# linesensor2b.net
KiCad netlist of a schematic drawn in EAGLE
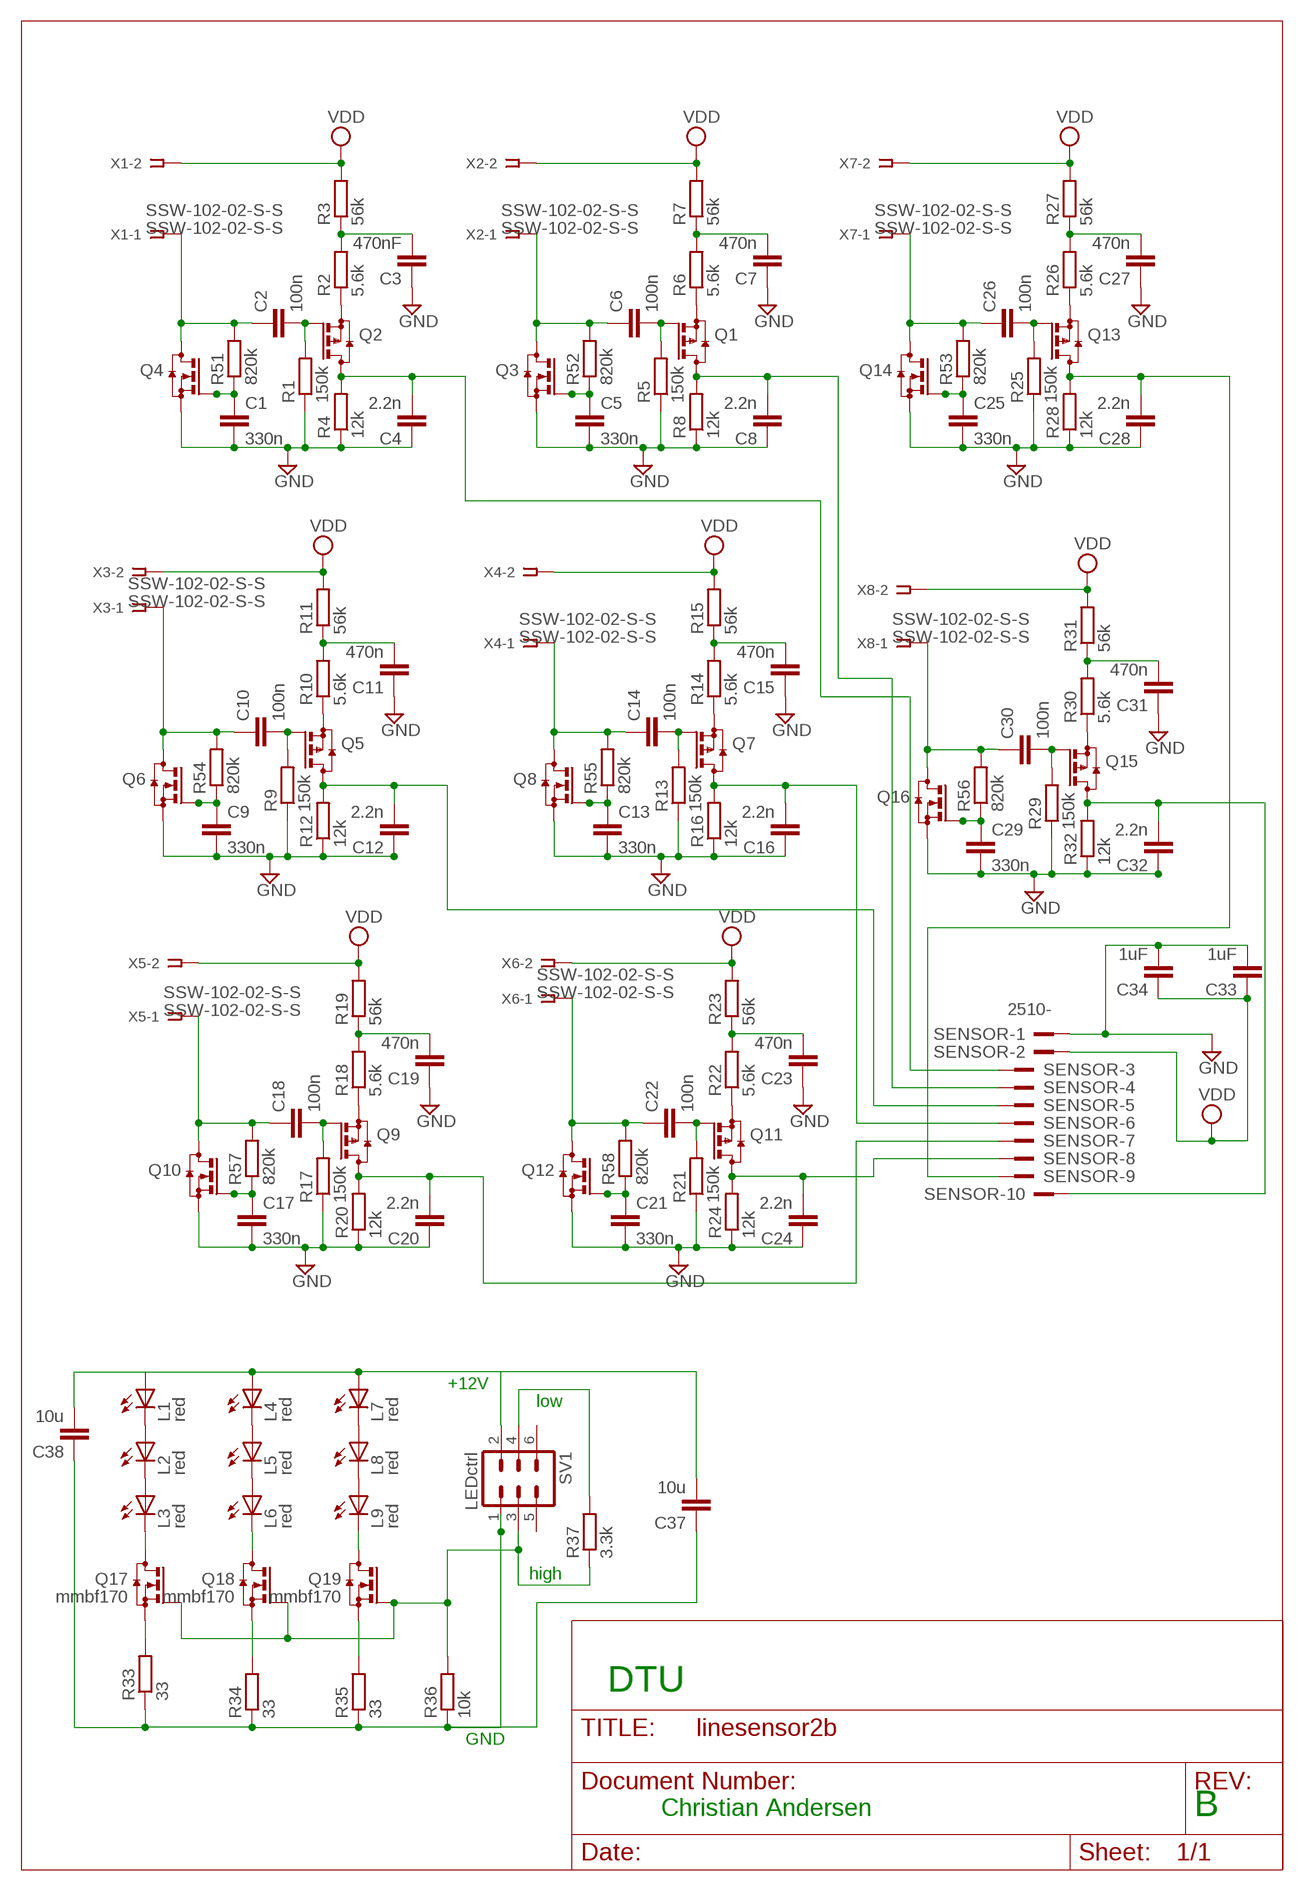
[diagram p0: schematic, sheet 1]

(export (version "E")
  (design (tool "Eeschema 10.0.6"))
  (components
    (comp (ref "C1")
      (value "330n")
      (footprint "eagle-import:C1206")
      (libsource (lib "eagle-import") (part "C-EUC1206"))
    )
    (comp (ref "C2")
      (value "100n")
      (footprint "eagle-import:C1206K")
      (libsource (lib "eagle-import") (part "C-EUC1206K"))
    )
    (comp (ref "C3")
      (value "470nF")
      (footprint "eagle-import:C1206K")
      (libsource (lib "eagle-import") (part "C-EUC1206K"))
    )
    (comp (ref "C4")
      (value "2.2n")
      (footprint "eagle-import:C1206")
      (libsource (lib "eagle-import") (part "CC1206"))
    )
    (comp (ref "C5")
      (value "330n")
      (footprint "eagle-import:C1206")
      (libsource (lib "eagle-import") (part "C-EUC1206"))
    )
    (comp (ref "C6")
      (value "100n")
      (footprint "eagle-import:C1206")
      (libsource (lib "eagle-import") (part "CC1206"))
    )
    (comp (ref "C7")
      (value "470n")
      (footprint "eagle-import:C1206")
      (libsource (lib "eagle-import") (part "C-EUC1206"))
    )
    (comp (ref "C8")
      (value "2.2n")
      (footprint "eagle-import:C1206")
      (libsource (lib "eagle-import") (part "CC1206"))
    )
    (comp (ref "C9")
      (value "330n")
      (footprint "eagle-import:C1206K")
      (libsource (lib "eagle-import") (part "C-EUC1206K"))
    )
    (comp (ref "C10")
      (value "100n")
      (footprint "eagle-import:C1206K")
      (libsource (lib "eagle-import") (part "C-EUC1206K"))
    )
    (comp (ref "C11")
      (value "470n")
      (footprint "eagle-import:C1206K")
      (libsource (lib "eagle-import") (part "C-EUC1206K"))
    )
    (comp (ref "C12")
      (value "2.2n")
      (footprint "eagle-import:C1206K")
      (libsource (lib "eagle-import") (part "C-EUC1206K"))
    )
    (comp (ref "C13")
      (value "330n")
      (footprint "eagle-import:C1206K")
      (libsource (lib "eagle-import") (part "C-EUC1206K"))
    )
    (comp (ref "C14")
      (value "100n")
      (footprint "eagle-import:C1206K")
      (libsource (lib "eagle-import") (part "C-EUC1206K"))
    )
    (comp (ref "C15")
      (value "470n")
      (footprint "eagle-import:C1206K")
      (libsource (lib "eagle-import") (part "C-EUC1206K"))
    )
    (comp (ref "C16")
      (value "2.2n")
      (footprint "eagle-import:C1206K")
      (libsource (lib "eagle-import") (part "C-EUC1206K"))
    )
    (comp (ref "C17")
      (value "330n")
      (footprint "eagle-import:C1206K")
      (libsource (lib "eagle-import") (part "C-EUC1206K"))
    )
    (comp (ref "C18")
      (value "100n")
      (footprint "eagle-import:C1206K")
      (libsource (lib "eagle-import") (part "C-EUC1206K"))
    )
    (comp (ref "C19")
      (value "470n")
      (footprint "eagle-import:C1206K")
      (libsource (lib "eagle-import") (part "C-EUC1206K"))
    )
    (comp (ref "C20")
      (value "2.2n")
      (footprint "eagle-import:C1206K")
      (libsource (lib "eagle-import") (part "C-EUC1206K"))
    )
    (comp (ref "C21")
      (value "330n")
      (footprint "eagle-import:C1206K")
      (libsource (lib "eagle-import") (part "C-EUC1206K"))
    )
    (comp (ref "C22")
      (value "100n")
      (footprint "eagle-import:C1206K")
      (libsource (lib "eagle-import") (part "C-EUC1206K"))
    )
    (comp (ref "C23")
      (value "470n")
      (footprint "eagle-import:C1206K")
      (libsource (lib "eagle-import") (part "C-EUC1206K"))
    )
    (comp (ref "C24")
      (value "2.2n")
      (footprint "eagle-import:C1206K")
      (libsource (lib "eagle-import") (part "C-EUC1206K"))
    )
    (comp (ref "C25")
      (value "330n")
      (footprint "eagle-import:C1206K")
      (libsource (lib "eagle-import") (part "C-EUC1206K"))
    )
    (comp (ref "C26")
      (value "100n")
      (footprint "eagle-import:C1206K")
      (libsource (lib "eagle-import") (part "C-EUC1206K"))
    )
    (comp (ref "C27")
      (value "470n")
      (footprint "eagle-import:C1206K")
      (libsource (lib "eagle-import") (part "C-EUC1206K"))
    )
    (comp (ref "C28")
      (value "2.2n")
      (footprint "eagle-import:C1206K")
      (libsource (lib "eagle-import") (part "C-EUC1206K"))
    )
    (comp (ref "C29")
      (value "330n")
      (footprint "eagle-import:C1206K")
      (libsource (lib "eagle-import") (part "C-EUC1206K"))
    )
    (comp (ref "C30")
      (value "100n")
      (footprint "eagle-import:C1206K")
      (libsource (lib "eagle-import") (part "C-EUC1206K"))
    )
    (comp (ref "C31")
      (value "470n")
      (footprint "eagle-import:C1206K")
      (libsource (lib "eagle-import") (part "C-EUC1206K"))
    )
    (comp (ref "C32")
      (value "2.2n")
      (footprint "eagle-import:C1206K")
      (libsource (lib "eagle-import") (part "C-EUC1206K"))
    )
    (comp (ref "C33")
      (value "1uF")
      (footprint "eagle-import:C1812")
      (libsource (lib "eagle-import") (part "CC1812"))
    )
    (comp (ref "C34")
      (value "1uF")
      (footprint "eagle-import:C1812")
      (libsource (lib "eagle-import") (part "CC1812"))
    )
    (comp (ref "C37")
      (value "10u")
      (footprint "eagle-import:C1206K")
      (libsource (lib "eagle-import") (part "C-EUC1206K"))
    )
    (comp (ref "C38")
      (value "10u")
      (footprint "eagle-import:C1206K")
      (libsource (lib "eagle-import") (part "C-EUC1206K"))
    )
    (comp (ref "L1")
      (value "red")
      (footprint "eagle-import:LED3MM")
      (libsource (lib "eagle-import") (part "LED3MM"))
    )
    (comp (ref "L2")
      (value "red")
      (footprint "eagle-import:LED3MM")
      (libsource (lib "eagle-import") (part "LED3MM"))
    )
    (comp (ref "L3")
      (value "red")
      (footprint "eagle-import:LED3MM")
      (libsource (lib "eagle-import") (part "LED3MM"))
    )
    (comp (ref "L4")
      (value "red")
      (footprint "eagle-import:LED3MM")
      (libsource (lib "eagle-import") (part "LED3MM"))
    )
    (comp (ref "L5")
      (value "red")
      (footprint "eagle-import:LED3MM")
      (libsource (lib "eagle-import") (part "LED3MM"))
    )
    (comp (ref "L6")
      (value "red")
      (footprint "eagle-import:LED3MM")
      (libsource (lib "eagle-import") (part "LED3MM"))
    )
    (comp (ref "L7")
      (value "red")
      (footprint "eagle-import:LED3MM")
      (libsource (lib "eagle-import") (part "LED3MM"))
    )
    (comp (ref "L8")
      (value "red")
      (footprint "eagle-import:LED3MM")
      (libsource (lib "eagle-import") (part "LED3MM"))
    )
    (comp (ref "L9")
      (value "red")
      (footprint "eagle-import:LED3MM")
      (libsource (lib "eagle-import") (part "LED3MM"))
    )
    (comp (ref "Q1")
      (value "BSS84")
      (footprint "eagle-import:SOT23")
      (libsource (lib "eagle-import") (part "BSS84"))
    )
    (comp (ref "Q2")
      (value "BSS84")
      (footprint "eagle-import:SOT23")
      (libsource (lib "eagle-import") (part "BSS84"))
    )
    (comp (ref "Q3")
      (value "BSS123")
      (footprint "eagle-import:SOT23")
      (libsource (lib "eagle-import") (part "BSS123"))
    )
    (comp (ref "Q4")
      (value "BSS123")
      (footprint "eagle-import:SOT23")
      (libsource (lib "eagle-import") (part "BSS123"))
    )
    (comp (ref "Q5")
      (value "BSS84")
      (footprint "eagle-import:SOT23")
      (libsource (lib "eagle-import") (part "BSS84"))
    )
    (comp (ref "Q6")
      (value "BSS123")
      (footprint "eagle-import:SOT23")
      (libsource (lib "eagle-import") (part "BSS123"))
    )
    (comp (ref "Q7")
      (value "BSS84")
      (footprint "eagle-import:SOT23")
      (libsource (lib "eagle-import") (part "BSS84"))
    )
    (comp (ref "Q8")
      (value "BSS123")
      (footprint "eagle-import:SOT23")
      (libsource (lib "eagle-import") (part "BSS123"))
    )
    (comp (ref "Q9")
      (value "BSS84")
      (footprint "eagle-import:SOT23")
      (libsource (lib "eagle-import") (part "BSS84"))
    )
    (comp (ref "Q10")
      (value "BSS123")
      (footprint "eagle-import:SOT23")
      (libsource (lib "eagle-import") (part "BSS123"))
    )
    (comp (ref "Q11")
      (value "BSS84")
      (footprint "eagle-import:SOT23")
      (libsource (lib "eagle-import") (part "BSS84"))
    )
    (comp (ref "Q12")
      (value "BSS123")
      (footprint "eagle-import:SOT23")
      (libsource (lib "eagle-import") (part "BSS123"))
    )
    (comp (ref "Q13")
      (value "BSS84")
      (footprint "eagle-import:SOT23")
      (libsource (lib "eagle-import") (part "BSS84"))
    )
    (comp (ref "Q14")
      (value "BSS123")
      (footprint "eagle-import:SOT23")
      (libsource (lib "eagle-import") (part "BSS123"))
    )
    (comp (ref "Q15")
      (value "BSS84")
      (footprint "eagle-import:SOT23")
      (libsource (lib "eagle-import") (part "BSS84"))
    )
    (comp (ref "Q16")
      (value "BSS123")
      (footprint "eagle-import:SOT23")
      (libsource (lib "eagle-import") (part "BSS123"))
    )
    (comp (ref "Q17")
      (value "mmbf170")
      (footprint "eagle-import:SOT23")
      (libsource (lib "eagle-import") (part "BSS123"))
    )
    (comp (ref "Q18")
      (value "mmbf170")
      (footprint "eagle-import:SOT23")
      (libsource (lib "eagle-import") (part "BSS123"))
    )
    (comp (ref "Q19")
      (value "mmbf170")
      (footprint "eagle-import:SOT23")
      (libsource (lib "eagle-import") (part "BSS123"))
    )
    (comp (ref "R1")
      (value "150k")
      (footprint "eagle-import:R1206")
      (libsource (lib "eagle-import") (part "RR1206"))
    )
    (comp (ref "R2")
      (value "5.6k")
      (footprint "eagle-import:R1206")
      (libsource (lib "eagle-import") (part "RR1206"))
    )
    (comp (ref "R3")
      (value "56k")
      (footprint "eagle-import:R1206")
      (libsource (lib "eagle-import") (part "RR1206"))
    )
    (comp (ref "R4")
      (value "12k")
      (footprint "eagle-import:R1206")
      (libsource (lib "eagle-import") (part "RR1206"))
    )
    (comp (ref "R5")
      (value "150k")
      (footprint "eagle-import:R1206")
      (libsource (lib "eagle-import") (part "RR1206"))
    )
    (comp (ref "R6")
      (value "5.6k")
      (footprint "eagle-import:R1206")
      (libsource (lib "eagle-import") (part "RR1206"))
    )
    (comp (ref "R7")
      (value "56k")
      (footprint "eagle-import:R1206")
      (libsource (lib "eagle-import") (part "RR1206"))
    )
    (comp (ref "R8")
      (value "12k")
      (footprint "eagle-import:R1206")
      (libsource (lib "eagle-import") (part "RR1206"))
    )
    (comp (ref "R9")
      (value "150k")
      (footprint "eagle-import:R1206")
      (libsource (lib "eagle-import") (part "R-EU_R1206"))
    )
    (comp (ref "R10")
      (value "5.6k")
      (footprint "eagle-import:R1206")
      (libsource (lib "eagle-import") (part "RR1206"))
    )
    (comp (ref "R11")
      (value "56k")
      (footprint "eagle-import:R1206")
      (libsource (lib "eagle-import") (part "RR1206"))
    )
    (comp (ref "R12")
      (value "12k")
      (footprint "eagle-import:R1206")
      (libsource (lib "eagle-import") (part "R-EU_R1206"))
    )
    (comp (ref "R13")
      (value "150k")
      (footprint "eagle-import:R1206")
      (libsource (lib "eagle-import") (part "R-EU_R1206"))
    )
    (comp (ref "R14")
      (value "5.6k")
      (footprint "eagle-import:R1206")
      (libsource (lib "eagle-import") (part "RR1206"))
    )
    (comp (ref "R15")
      (value "56k")
      (footprint "eagle-import:R1206")
      (libsource (lib "eagle-import") (part "RR1206"))
    )
    (comp (ref "R16")
      (value "12k")
      (footprint "eagle-import:R1206")
      (libsource (lib "eagle-import") (part "R-EU_R1206"))
    )
    (comp (ref "R17")
      (value "150k")
      (footprint "eagle-import:R1206")
      (libsource (lib "eagle-import") (part "R-EU_R1206"))
    )
    (comp (ref "R18")
      (value "5.6k")
      (footprint "eagle-import:R1206")
      (libsource (lib "eagle-import") (part "R-EU_R1206"))
    )
    (comp (ref "R19")
      (value "56k")
      (footprint "eagle-import:R1206")
      (libsource (lib "eagle-import") (part "R-EU_R1206"))
    )
    (comp (ref "R20")
      (value "12k")
      (footprint "eagle-import:R1206")
      (libsource (lib "eagle-import") (part "R-EU_R1206"))
    )
    (comp (ref "R21")
      (value "150k")
      (footprint "eagle-import:R1206")
      (libsource (lib "eagle-import") (part "R-EU_R1206"))
    )
    (comp (ref "R22")
      (value "5.6k")
      (footprint "eagle-import:R1206")
      (libsource (lib "eagle-import") (part "R-EU_R1206"))
    )
    (comp (ref "R23")
      (value "56k")
      (footprint "eagle-import:R1206")
      (libsource (lib "eagle-import") (part "R-EU_R1206"))
    )
    (comp (ref "R24")
      (value "12k")
      (footprint "eagle-import:R1206")
      (libsource (lib "eagle-import") (part "R-EU_R1206"))
    )
    (comp (ref "R25")
      (value "150k")
      (footprint "eagle-import:R1206")
      (libsource (lib "eagle-import") (part "RR1206"))
    )
    (comp (ref "R26")
      (value "5.6k")
      (footprint "eagle-import:R1206")
      (libsource (lib "eagle-import") (part "RR1206"))
    )
    (comp (ref "R27")
      (value "56k")
      (footprint "eagle-import:R1206")
      (libsource (lib "eagle-import") (part "RR1206"))
    )
    (comp (ref "R28")
      (value "12k")
      (footprint "eagle-import:R1206")
      (libsource (lib "eagle-import") (part "RR1206"))
    )
    (comp (ref "R29")
      (value "150k")
      (footprint "eagle-import:R1206")
      (libsource (lib "eagle-import") (part "RR1206"))
    )
    (comp (ref "R30")
      (value "5.6k")
      (footprint "eagle-import:R1206")
      (libsource (lib "eagle-import") (part "RR1206"))
    )
    (comp (ref "R31")
      (value "56k")
      (footprint "eagle-import:R1206")
      (libsource (lib "eagle-import") (part "RR1206"))
    )
    (comp (ref "R32")
      (value "12k")
      (footprint "eagle-import:R1206")
      (libsource (lib "eagle-import") (part "RR1206"))
    )
    (comp (ref "R33")
      (value "33")
      (footprint "eagle-import:R1206")
      (libsource (lib "eagle-import") (part "RR1206"))
    )
    (comp (ref "R34")
      (value "33")
      (footprint "eagle-import:R1206")
      (libsource (lib "eagle-import") (part "RR1206"))
    )
    (comp (ref "R35")
      (value "33")
      (footprint "eagle-import:R1206")
      (libsource (lib "eagle-import") (part "RR1206"))
    )
    (comp (ref "R36")
      (value "10k")
      (footprint "eagle-import:R1206")
      (libsource (lib "eagle-import") (part "RR1206"))
    )
    (comp (ref "R37")
      (value "3.3k")
      (footprint "eagle-import:R1206")
      (libsource (lib "eagle-import") (part "RR1206"))
    )
    (comp (ref "R51")
      (value "820k")
      (footprint "eagle-import:R1206")
      (libsource (lib "eagle-import") (part "RR1206"))
    )
    (comp (ref "R52")
      (value "820k")
      (footprint "eagle-import:R1206")
      (libsource (lib "eagle-import") (part "RR1206"))
    )
    (comp (ref "R53")
      (value "820k")
      (footprint "eagle-import:R1206")
      (libsource (lib "eagle-import") (part "RR1206"))
    )
    (comp (ref "R54")
      (value "820k")
      (footprint "eagle-import:R1206")
      (libsource (lib "eagle-import") (part "R-EU_R1206"))
    )
    (comp (ref "R55")
      (value "820k")
      (footprint "eagle-import:R1206")
      (libsource (lib "eagle-import") (part "RR1206"))
    )
    (comp (ref "R56")
      (value "820k")
      (footprint "eagle-import:R1206")
      (libsource (lib "eagle-import") (part "RR1206"))
    )
    (comp (ref "R57")
      (value "820k")
      (footprint "eagle-import:R1206")
      (libsource (lib "eagle-import") (part "R-EU_R1206"))
    )
    (comp (ref "R58")
      (value "820k")
      (footprint "eagle-import:R1206")
      (libsource (lib "eagle-import") (part "R-EU_R1206"))
    )
    (comp (ref "SENSOR")
      (value "2510-")
      (footprint "eagle-import:PAK100_2500-10")
      (fields (field (name "MF") "3M") (field (name "MPN") "2510-6002UB"))
      (libsource (lib "eagle-import") (part "2510-"))
    )
    (comp (ref "SV1")
      (value "LEDctrl")
      (footprint "eagle-import:MA03-2")
      (libsource (lib "eagle-import") (part "MA03-2"))
    )
    (comp (ref "X1")
      (value "SSW-102-02-S-S")
      (footprint "eagle-import:SSW-102-02-S-S")
      (fields (field (name "MPN") "SSW-102-02-S-S"))
      (libsource (lib "eagle-import") (part "SSW-102-02-S-S"))
    )
    (comp (ref "X2")
      (value "SSW-102-02-S-S")
      (footprint "eagle-import:SSW-102-02-S-S")
      (fields (field (name "MPN") "SSW-102-02-S-S"))
      (libsource (lib "eagle-import") (part "SSW-102-02-S-S"))
    )
    (comp (ref "X3")
      (value "SSW-102-02-S-S")
      (footprint "eagle-import:SSW-102-02-S-S")
      (fields (field (name "MPN") "SSW-102-02-S-S"))
      (libsource (lib "eagle-import") (part "SSW-102-02-S-S"))
    )
    (comp (ref "X4")
      (value "SSW-102-02-S-S")
      (footprint "eagle-import:SSW-102-02-S-S")
      (fields (field (name "MPN") "SSW-102-02-S-S"))
      (libsource (lib "eagle-import") (part "SSW-102-02-S-S"))
    )
    (comp (ref "X5")
      (value "SSW-102-02-S-S")
      (footprint "eagle-import:SSW-102-02-S-S")
      (fields (field (name "MPN") "SSW-102-02-S-S"))
      (libsource (lib "eagle-import") (part "SSW-102-02-S-S"))
    )
    (comp (ref "X6")
      (value "SSW-102-02-S-S")
      (footprint "eagle-import:SSW-102-02-S-S")
      (fields (field (name "MPN") "SSW-102-02-S-S"))
      (libsource (lib "eagle-import") (part "SSW-102-02-S-S"))
    )
    (comp (ref "X7")
      (value "SSW-102-02-S-S")
      (footprint "eagle-import:SSW-102-02-S-S")
      (fields (field (name "MPN") "SSW-102-02-S-S"))
      (libsource (lib "eagle-import") (part "SSW-102-02-S-S"))
    )
    (comp (ref "X8")
      (value "SSW-102-02-S-S")
      (footprint "eagle-import:SSW-102-02-S-S")
      (fields (field (name "MPN") "SSW-102-02-S-S"))
      (libsource (lib "eagle-import") (part "SSW-102-02-S-S"))
    )
  )
  (nets
    (net (code "1") (name "GND") (class "Default")
      (node (ref "C1") (pin "2") (pinfunction "2_2") (pintype "passive"))
      (node (ref "C11") (pin "1") (pinfunction "1_1") (pintype "passive"))
      (node (ref "C12") (pin "1") (pinfunction "1_1") (pintype "passive"))
      (node (ref "C13") (pin "2") (pinfunction "2_2") (pintype "passive"))
      (node (ref "C15") (pin "1") (pinfunction "1_1") (pintype "passive"))
      (node (ref "C16") (pin "1") (pinfunction "1_1") (pintype "passive"))
      (node (ref "C17") (pin "2") (pinfunction "2_2") (pintype "passive"))
      (node (ref "C19") (pin "1") (pinfunction "1_1") (pintype "passive"))
      (node (ref "C20") (pin "1") (pinfunction "1_1") (pintype "passive"))
      (node (ref "C21") (pin "2") (pinfunction "2_2") (pintype "passive"))
      (node (ref "C23") (pin "1") (pinfunction "1_1") (pintype "passive"))
      (node (ref "C24") (pin "1") (pinfunction "1_1") (pintype "passive"))
      (node (ref "C25") (pin "2") (pinfunction "2_2") (pintype "passive"))
      (node (ref "C27") (pin "1") (pinfunction "1_1") (pintype "passive"))
      (node (ref "C28") (pin "1") (pinfunction "1_1") (pintype "passive"))
      (node (ref "C29") (pin "2") (pinfunction "2_2") (pintype "passive"))
      (node (ref "C3") (pin "1") (pinfunction "1_1") (pintype "passive"))
      (node (ref "C31") (pin "1") (pinfunction "1_1") (pintype "passive"))
      (node (ref "C32") (pin "1") (pinfunction "1_1") (pintype "passive"))
      (node (ref "C33") (pin "2") (pinfunction "2_2") (pintype "passive"))
      (node (ref "C34") (pin "2") (pinfunction "2_2") (pintype "passive"))
      (node (ref "C4") (pin "1") (pinfunction "1_1") (pintype "passive"))
      (node (ref "C5") (pin "2") (pinfunction "2_2") (pintype "passive"))
      (node (ref "C7") (pin "1") (pinfunction "1_1") (pintype "passive"))
      (node (ref "C8") (pin "1") (pinfunction "1_1") (pintype "passive"))
      (node (ref "C9") (pin "2") (pinfunction "2_2") (pintype "passive"))
      (node (ref "Q10") (pin "2") (pinfunction "S_2") (pintype "passive"))
      (node (ref "Q12") (pin "2") (pinfunction "S_2") (pintype "passive"))
      (node (ref "Q14") (pin "2") (pinfunction "S_2") (pintype "passive"))
      (node (ref "Q16") (pin "2") (pinfunction "S_2") (pintype "passive"))
      (node (ref "Q3") (pin "2") (pinfunction "S_2") (pintype "passive"))
      (node (ref "Q4") (pin "2") (pinfunction "S_2") (pintype "passive"))
      (node (ref "Q6") (pin "2") (pinfunction "S_2") (pintype "passive"))
      (node (ref "Q8") (pin "2") (pinfunction "S_2") (pintype "passive"))
      (node (ref "R1") (pin "1") (pinfunction "1_1") (pintype "passive"))
      (node (ref "R12") (pin "1") (pinfunction "1_1") (pintype "passive"))
      (node (ref "R13") (pin "1") (pinfunction "1_1") (pintype "passive"))
      (node (ref "R16") (pin "1") (pinfunction "1_1") (pintype "passive"))
      (node (ref "R17") (pin "1") (pinfunction "1_1") (pintype "passive"))
      (node (ref "R20") (pin "1") (pinfunction "1_1") (pintype "passive"))
      (node (ref "R21") (pin "1") (pinfunction "1_1") (pintype "passive"))
      (node (ref "R24") (pin "1") (pinfunction "1_1") (pintype "passive"))
      (node (ref "R25") (pin "1") (pinfunction "1_1") (pintype "passive"))
      (node (ref "R28") (pin "1") (pinfunction "1_1") (pintype "passive"))
      (node (ref "R29") (pin "1") (pinfunction "1_1") (pintype "passive"))
      (node (ref "R32") (pin "1") (pinfunction "1_1") (pintype "passive"))
      (node (ref "R4") (pin "1") (pinfunction "1_1") (pintype "passive"))
      (node (ref "R5") (pin "1") (pinfunction "1_1") (pintype "passive"))
      (node (ref "R8") (pin "1") (pinfunction "1_1") (pintype "passive"))
      (node (ref "R9") (pin "1") (pinfunction "1_1") (pintype "passive"))
      (node (ref "SENSOR") (pin "1") (pinfunction "KL_1") (pintype "passive"))
    )
    (net (code "2") (name "Net-(C3-Pad2)") (class "Default")
      (node (ref "C3") (pin "2") (pinfunction "2_2") (pintype "passive"))
      (node (ref "R2") (pin "2") (pinfunction "2_2") (pintype "passive"))
      (node (ref "R3") (pin "1") (pinfunction "1_1") (pintype "passive"))
    )
    (net (code "3") (name "Net-(C7-Pad2)") (class "Default")
      (node (ref "C7") (pin "2") (pinfunction "2_2") (pintype "passive"))
      (node (ref "R6") (pin "2") (pinfunction "2_2") (pintype "passive"))
      (node (ref "R7") (pin "1") (pinfunction "1_1") (pintype "passive"))
    )
    (net (code "4") (name "Net-(C11-Pad2)") (class "Default")
      (node (ref "C11") (pin "2") (pinfunction "2_2") (pintype "passive"))
      (node (ref "R10") (pin "2") (pinfunction "2_2") (pintype "passive"))
      (node (ref "R11") (pin "1") (pinfunction "1_1") (pintype "passive"))
    )
    (net (code "5") (name "Net-(C15-Pad2)") (class "Default")
      (node (ref "C15") (pin "2") (pinfunction "2_2") (pintype "passive"))
      (node (ref "R14") (pin "2") (pinfunction "2_2") (pintype "passive"))
      (node (ref "R15") (pin "1") (pinfunction "1_1") (pintype "passive"))
    )
    (net (code "6") (name "Net-(C19-Pad2)") (class "Default")
      (node (ref "C19") (pin "2") (pinfunction "2_2") (pintype "passive"))
      (node (ref "R18") (pin "2") (pinfunction "2_2") (pintype "passive"))
      (node (ref "R19") (pin "1") (pinfunction "1_1") (pintype "passive"))
    )
    (net (code "7") (name "Net-(C23-Pad2)") (class "Default")
      (node (ref "C23") (pin "2") (pinfunction "2_2") (pintype "passive"))
      (node (ref "R22") (pin "2") (pinfunction "2_2") (pintype "passive"))
      (node (ref "R23") (pin "1") (pinfunction "1_1") (pintype "passive"))
    )
    (net (code "8") (name "Net-(C27-Pad2)") (class "Default")
      (node (ref "C27") (pin "2") (pinfunction "2_2") (pintype "passive"))
      (node (ref "R26") (pin "2") (pinfunction "2_2") (pintype "passive"))
      (node (ref "R27") (pin "1") (pinfunction "1_1") (pintype "passive"))
    )
    (net (code "9") (name "Net-(C31-Pad2)") (class "Default")
      (node (ref "C31") (pin "2") (pinfunction "2_2") (pintype "passive"))
      (node (ref "R30") (pin "2") (pinfunction "2_2") (pintype "passive"))
      (node (ref "R31") (pin "1") (pinfunction "1_1") (pintype "passive"))
    )
    (net (code "10") (name "Net-(C37-Pad1)") (class "Default")
      (node (ref "C37") (pin "1") (pinfunction "1_1") (pintype "passive"))
      (node (ref "C38") (pin "1") (pinfunction "1_1") (pintype "passive"))
      (node (ref "R33") (pin "1") (pinfunction "1_1") (pintype "passive"))
      (node (ref "R34") (pin "1") (pinfunction "1_1") (pintype "passive"))
      (node (ref "R35") (pin "1") (pinfunction "1_1") (pintype "passive"))
      (node (ref "R36") (pin "1") (pinfunction "1_1") (pintype "passive"))
      (node (ref "SV1") (pin "1") (pinfunction "1_1") (pintype "passive"))
    )
    (net (code "11") (name "Net-(C37-Pad2)") (class "Default")
      (node (ref "C37") (pin "2") (pinfunction "2_2") (pintype "passive"))
      (node (ref "C38") (pin "2") (pinfunction "2_2") (pintype "passive"))
      (node (ref "L1") (pin "A") (pinfunction "A_A") (pintype "passive"))
      (node (ref "L4") (pin "A") (pinfunction "A_A") (pintype "passive"))
      (node (ref "L7") (pin "A") (pinfunction "A_A") (pintype "passive"))
      (node (ref "SV1") (pin "2") (pinfunction "2_2") (pintype "passive"))
    )
    (net (code "12") (name "Net-(L1-C)") (class "Default")
      (node (ref "L1") (pin "K") (pinfunction "C_K") (pintype "passive"))
      (node (ref "L2") (pin "A") (pinfunction "A_A") (pintype "passive"))
    )
    (net (code "13") (name "Net-(L2-C)") (class "Default")
      (node (ref "L2") (pin "K") (pinfunction "C_K") (pintype "passive"))
      (node (ref "L3") (pin "A") (pinfunction "A_A") (pintype "passive"))
    )
    (net (code "14") (name "Net-(L3-C)") (class "Default")
      (node (ref "L3") (pin "K") (pinfunction "C_K") (pintype "passive"))
      (node (ref "Q17") (pin "3") (pinfunction "D_3") (pintype "passive"))
    )
    (net (code "15") (name "Net-(L4-C)") (class "Default")
      (node (ref "L4") (pin "K") (pinfunction "C_K") (pintype "passive"))
      (node (ref "L5") (pin "A") (pinfunction "A_A") (pintype "passive"))
    )
    (net (code "16") (name "Net-(L5-C)") (class "Default")
      (node (ref "L5") (pin "K") (pinfunction "C_K") (pintype "passive"))
      (node (ref "L6") (pin "A") (pinfunction "A_A") (pintype "passive"))
    )
    (net (code "17") (name "Net-(L6-C)") (class "Default")
      (node (ref "L6") (pin "K") (pinfunction "C_K") (pintype "passive"))
      (node (ref "Q18") (pin "3") (pinfunction "D_3") (pintype "passive"))
    )
    (net (code "18") (name "Net-(L7-C)") (class "Default")
      (node (ref "L7") (pin "K") (pinfunction "C_K") (pintype "passive"))
      (node (ref "L8") (pin "A") (pinfunction "A_A") (pintype "passive"))
    )
    (net (code "19") (name "Net-(L8-C)") (class "Default")
      (node (ref "L8") (pin "K") (pinfunction "C_K") (pintype "passive"))
      (node (ref "L9") (pin "A") (pinfunction "A_A") (pintype "passive"))
    )
    (net (code "20") (name "Net-(L9-C)") (class "Default")
      (node (ref "L9") (pin "K") (pinfunction "C_K") (pintype "passive"))
      (node (ref "Q19") (pin "3") (pinfunction "D_3") (pintype "passive"))
    )
    (net (code "21") (name "Net-(Q1-D)") (class "Default")
      (node (ref "C8") (pin "2") (pinfunction "2_2") (pintype "passive"))
      (node (ref "Q1") (pin "3") (pinfunction "D_3") (pintype "passive"))
      (node (ref "R8") (pin "2") (pinfunction "2_2") (pintype "passive"))
      (node (ref "SENSOR") (pin "4") (pinfunction "KL_4") (pintype "passive"))
    )
    (net (code "22") (name "Net-(Q1-G)") (class "Default")
      (node (ref "C6") (pin "2") (pinfunction "2_2") (pintype "passive"))
      (node (ref "Q1") (pin "1") (pinfunction "G_1") (pintype "passive"))
      (node (ref "R5") (pin "2") (pinfunction "2_2") (pintype "passive"))
    )
    (net (code "23") (name "Net-(Q1-S)") (class "Default")
      (node (ref "Q1") (pin "2") (pinfunction "S_2") (pintype "passive"))
      (node (ref "R6") (pin "1") (pinfunction "1_1") (pintype "passive"))
    )
    (net (code "24") (name "Net-(Q2-D)") (class "Default")
      (node (ref "C4") (pin "2") (pinfunction "2_2") (pintype "passive"))
      (node (ref "Q2") (pin "3") (pinfunction "D_3") (pintype "passive"))
      (node (ref "R4") (pin "2") (pinfunction "2_2") (pintype "passive"))
      (node (ref "SENSOR") (pin "3") (pinfunction "KL_3") (pintype "passive"))
    )
    (net (code "25") (name "Net-(Q2-G)") (class "Default")
      (node (ref "C2") (pin "2") (pinfunction "2_2") (pintype "passive"))
      (node (ref "Q2") (pin "1") (pinfunction "G_1") (pintype "passive"))
      (node (ref "R1") (pin "2") (pinfunction "2_2") (pintype "passive"))
    )
    (net (code "26") (name "Net-(Q2-S)") (class "Default")
      (node (ref "Q2") (pin "2") (pinfunction "S_2") (pintype "passive"))
      (node (ref "R2") (pin "1") (pinfunction "1_1") (pintype "passive"))
    )
    (net (code "27") (name "Net-(Q3-D)") (class "Default")
      (node (ref "C6") (pin "1") (pinfunction "1_1") (pintype "passive"))
      (node (ref "Q3") (pin "3") (pinfunction "D_3") (pintype "passive"))
      (node (ref "R52") (pin "2") (pinfunction "2_2") (pintype "passive"))
      (node (ref "X2") (pin "1") (pinfunction "1_1") (pintype "passive"))
    )
    (net (code "28") (name "Net-(Q3-G)") (class "Default")
      (node (ref "C5") (pin "1") (pinfunction "1_1") (pintype "passive"))
      (node (ref "Q3") (pin "1") (pinfunction "G_1") (pintype "passive"))
      (node (ref "R52") (pin "1") (pinfunction "1_1") (pintype "passive"))
    )
    (net (code "29") (name "Net-(Q4-D)") (class "Default")
      (node (ref "C2") (pin "1") (pinfunction "1_1") (pintype "passive"))
      (node (ref "Q4") (pin "3") (pinfunction "D_3") (pintype "passive"))
      (node (ref "R51") (pin "2") (pinfunction "2_2") (pintype "passive"))
      (node (ref "X1") (pin "1") (pinfunction "1_1") (pintype "passive"))
    )
    (net (code "30") (name "Net-(Q4-G)") (class "Default")
      (node (ref "C1") (pin "1") (pinfunction "1_1") (pintype "passive"))
      (node (ref "Q4") (pin "1") (pinfunction "G_1") (pintype "passive"))
      (node (ref "R51") (pin "1") (pinfunction "1_1") (pintype "passive"))
    )
    (net (code "31") (name "Net-(Q5-D)") (class "Default")
      (node (ref "C12") (pin "2") (pinfunction "2_2") (pintype "passive"))
      (node (ref "Q5") (pin "3") (pinfunction "D_3") (pintype "passive"))
      (node (ref "R12") (pin "2") (pinfunction "2_2") (pintype "passive"))
      (node (ref "SENSOR") (pin "5") (pinfunction "KL_5") (pintype "passive"))
    )
    (net (code "32") (name "Net-(Q5-G)") (class "Default")
      (node (ref "C10") (pin "2") (pinfunction "2_2") (pintype "passive"))
      (node (ref "Q5") (pin "1") (pinfunction "G_1") (pintype "passive"))
      (node (ref "R9") (pin "2") (pinfunction "2_2") (pintype "passive"))
    )
    (net (code "33") (name "Net-(Q5-S)") (class "Default")
      (node (ref "Q5") (pin "2") (pinfunction "S_2") (pintype "passive"))
      (node (ref "R10") (pin "1") (pinfunction "1_1") (pintype "passive"))
    )
    (net (code "34") (name "Net-(Q6-D)") (class "Default")
      (node (ref "C10") (pin "1") (pinfunction "1_1") (pintype "passive"))
      (node (ref "Q6") (pin "3") (pinfunction "D_3") (pintype "passive"))
      (node (ref "R54") (pin "2") (pinfunction "2_2") (pintype "passive"))
      (node (ref "X3") (pin "1") (pinfunction "1_1") (pintype "passive"))
    )
    (net (code "35") (name "Net-(Q6-G)") (class "Default")
      (node (ref "C9") (pin "1") (pinfunction "1_1") (pintype "passive"))
      (node (ref "Q6") (pin "1") (pinfunction "G_1") (pintype "passive"))
      (node (ref "R54") (pin "1") (pinfunction "1_1") (pintype "passive"))
    )
    (net (code "36") (name "Net-(Q7-D)") (class "Default")
      (node (ref "C16") (pin "2") (pinfunction "2_2") (pintype "passive"))
      (node (ref "Q7") (pin "3") (pinfunction "D_3") (pintype "passive"))
      (node (ref "R16") (pin "2") (pinfunction "2_2") (pintype "passive"))
      (node (ref "SENSOR") (pin "6") (pinfunction "KL_6") (pintype "passive"))
    )
    (net (code "37") (name "Net-(Q7-G)") (class "Default")
      (node (ref "C14") (pin "2") (pinfunction "2_2") (pintype "passive"))
      (node (ref "Q7") (pin "1") (pinfunction "G_1") (pintype "passive"))
      (node (ref "R13") (pin "2") (pinfunction "2_2") (pintype "passive"))
    )
    (net (code "38") (name "Net-(Q7-S)") (class "Default")
      (node (ref "Q7") (pin "2") (pinfunction "S_2") (pintype "passive"))
      (node (ref "R14") (pin "1") (pinfunction "1_1") (pintype "passive"))
    )
    (net (code "39") (name "Net-(Q8-D)") (class "Default")
      (node (ref "C14") (pin "1") (pinfunction "1_1") (pintype "passive"))
      (node (ref "Q8") (pin "3") (pinfunction "D_3") (pintype "passive"))
      (node (ref "R55") (pin "2") (pinfunction "2_2") (pintype "passive"))
      (node (ref "X4") (pin "1") (pinfunction "1_1") (pintype "passive"))
    )
    (net (code "40") (name "Net-(Q8-G)") (class "Default")
      (node (ref "C13") (pin "1") (pinfunction "1_1") (pintype "passive"))
      (node (ref "Q8") (pin "1") (pinfunction "G_1") (pintype "passive"))
      (node (ref "R55") (pin "1") (pinfunction "1_1") (pintype "passive"))
    )
    (net (code "41") (name "Net-(Q9-D)") (class "Default")
      (node (ref "C20") (pin "2") (pinfunction "2_2") (pintype "passive"))
      (node (ref "Q9") (pin "3") (pinfunction "D_3") (pintype "passive"))
      (node (ref "R20") (pin "2") (pinfunction "2_2") (pintype "passive"))
      (node (ref "SENSOR") (pin "7") (pinfunction "KL_7") (pintype "passive"))
    )
    (net (code "42") (name "Net-(Q9-G)") (class "Default")
      (node (ref "C18") (pin "2") (pinfunction "2_2") (pintype "passive"))
      (node (ref "Q9") (pin "1") (pinfunction "G_1") (pintype "passive"))
      (node (ref "R17") (pin "2") (pinfunction "2_2") (pintype "passive"))
    )
    (net (code "43") (name "Net-(Q9-S)") (class "Default")
      (node (ref "Q9") (pin "2") (pinfunction "S_2") (pintype "passive"))
      (node (ref "R18") (pin "1") (pinfunction "1_1") (pintype "passive"))
    )
    (net (code "44") (name "Net-(Q10-D)") (class "Default")
      (node (ref "C18") (pin "1") (pinfunction "1_1") (pintype "passive"))
      (node (ref "Q10") (pin "3") (pinfunction "D_3") (pintype "passive"))
      (node (ref "R57") (pin "2") (pinfunction "2_2") (pintype "passive"))
      (node (ref "X5") (pin "1") (pinfunction "1_1") (pintype "passive"))
    )
    (net (code "45") (name "Net-(Q10-G)") (class "Default")
      (node (ref "C17") (pin "1") (pinfunction "1_1") (pintype "passive"))
      (node (ref "Q10") (pin "1") (pinfunction "G_1") (pintype "passive"))
      (node (ref "R57") (pin "1") (pinfunction "1_1") (pintype "passive"))
    )
    (net (code "46") (name "Net-(Q11-D)") (class "Default")
      (node (ref "C24") (pin "2") (pinfunction "2_2") (pintype "passive"))
      (node (ref "Q11") (pin "3") (pinfunction "D_3") (pintype "passive"))
      (node (ref "R24") (pin "2") (pinfunction "2_2") (pintype "passive"))
      (node (ref "SENSOR") (pin "8") (pinfunction "KL_8") (pintype "passive"))
    )
    (net (code "47") (name "Net-(Q11-G)") (class "Default")
      (node (ref "C22") (pin "2") (pinfunction "2_2") (pintype "passive"))
      (node (ref "Q11") (pin "1") (pinfunction "G_1") (pintype "passive"))
      (node (ref "R21") (pin "2") (pinfunction "2_2") (pintype "passive"))
    )
    (net (code "48") (name "Net-(Q11-S)") (class "Default")
      (node (ref "Q11") (pin "2") (pinfunction "S_2") (pintype "passive"))
      (node (ref "R22") (pin "1") (pinfunction "1_1") (pintype "passive"))
    )
    (net (code "49") (name "Net-(Q12-D)") (class "Default")
      (node (ref "C22") (pin "1") (pinfunction "1_1") (pintype "passive"))
      (node (ref "Q12") (pin "3") (pinfunction "D_3") (pintype "passive"))
      (node (ref "R58") (pin "2") (pinfunction "2_2") (pintype "passive"))
      (node (ref "X6") (pin "1") (pinfunction "1_1") (pintype "passive"))
    )
    (net (code "50") (name "Net-(Q12-G)") (class "Default")
      (node (ref "C21") (pin "1") (pinfunction "1_1") (pintype "passive"))
      (node (ref "Q12") (pin "1") (pinfunction "G_1") (pintype "passive"))
      (node (ref "R58") (pin "1") (pinfunction "1_1") (pintype "passive"))
    )
    (net (code "51") (name "Net-(Q13-D)") (class "Default")
      (node (ref "C28") (pin "2") (pinfunction "2_2") (pintype "passive"))
      (node (ref "Q13") (pin "3") (pinfunction "D_3") (pintype "passive"))
      (node (ref "R28") (pin "2") (pinfunction "2_2") (pintype "passive"))
      (node (ref "SENSOR") (pin "9") (pinfunction "KL_9") (pintype "passive"))
    )
    (net (code "52") (name "Net-(Q13-G)") (class "Default")
      (node (ref "C26") (pin "2") (pinfunction "2_2") (pintype "passive"))
      (node (ref "Q13") (pin "1") (pinfunction "G_1") (pintype "passive"))
      (node (ref "R25") (pin "2") (pinfunction "2_2") (pintype "passive"))
    )
    (net (code "53") (name "Net-(Q13-S)") (class "Default")
      (node (ref "Q13") (pin "2") (pinfunction "S_2") (pintype "passive"))
      (node (ref "R26") (pin "1") (pinfunction "1_1") (pintype "passive"))
    )
    (net (code "54") (name "Net-(Q14-D)") (class "Default")
      (node (ref "C26") (pin "1") (pinfunction "1_1") (pintype "passive"))
      (node (ref "Q14") (pin "3") (pinfunction "D_3") (pintype "passive"))
      (node (ref "R53") (pin "2") (pinfunction "2_2") (pintype "passive"))
      (node (ref "X7") (pin "1") (pinfunction "1_1") (pintype "passive"))
    )
    (net (code "55") (name "Net-(Q14-G)") (class "Default")
      (node (ref "C25") (pin "1") (pinfunction "1_1") (pintype "passive"))
      (node (ref "Q14") (pin "1") (pinfunction "G_1") (pintype "passive"))
      (node (ref "R53") (pin "1") (pinfunction "1_1") (pintype "passive"))
    )
    (net (code "56") (name "Net-(Q15-D)") (class "Default")
      (node (ref "C32") (pin "2") (pinfunction "2_2") (pintype "passive"))
      (node (ref "Q15") (pin "3") (pinfunction "D_3") (pintype "passive"))
      (node (ref "R32") (pin "2") (pinfunction "2_2") (pintype "passive"))
      (node (ref "SENSOR") (pin "10") (pinfunction "KL_10") (pintype "passive"))
    )
    (net (code "57") (name "Net-(Q15-G)") (class "Default")
      (node (ref "C30") (pin "2") (pinfunction "2_2") (pintype "passive"))
      (node (ref "Q15") (pin "1") (pinfunction "G_1") (pintype "passive"))
      (node (ref "R29") (pin "2") (pinfunction "2_2") (pintype "passive"))
    )
    (net (code "58") (name "Net-(Q15-S)") (class "Default")
      (node (ref "Q15") (pin "2") (pinfunction "S_2") (pintype "passive"))
      (node (ref "R30") (pin "1") (pinfunction "1_1") (pintype "passive"))
    )
    (net (code "59") (name "Net-(Q16-D)") (class "Default")
      (node (ref "C30") (pin "1") (pinfunction "1_1") (pintype "passive"))
      (node (ref "Q16") (pin "3") (pinfunction "D_3") (pintype "passive"))
      (node (ref "R56") (pin "2") (pinfunction "2_2") (pintype "passive"))
      (node (ref "X8") (pin "1") (pinfunction "1_1") (pintype "passive"))
    )
    (net (code "60") (name "Net-(Q16-G)") (class "Default")
      (node (ref "C29") (pin "1") (pinfunction "1_1") (pintype "passive"))
      (node (ref "Q16") (pin "1") (pinfunction "G_1") (pintype "passive"))
      (node (ref "R56") (pin "1") (pinfunction "1_1") (pintype "passive"))
    )
    (net (code "61") (name "Net-(Q17-G)") (class "Default")
      (node (ref "Q17") (pin "1") (pinfunction "G_1") (pintype "passive"))
      (node (ref "Q18") (pin "1") (pinfunction "G_1") (pintype "passive"))
      (node (ref "Q19") (pin "1") (pinfunction "G_1") (pintype "passive"))
      (node (ref "R36") (pin "2") (pinfunction "2_2") (pintype "passive"))
      (node (ref "R37") (pin "1") (pinfunction "1_1") (pintype "passive"))
      (node (ref "SV1") (pin "3") (pinfunction "3_3") (pintype "passive"))
    )
    (net (code "62") (name "Net-(Q17-S)") (class "Default")
      (node (ref "Q17") (pin "2") (pinfunction "S_2") (pintype "passive"))
      (node (ref "R33") (pin "2") (pinfunction "2_2") (pintype "passive"))
    )
    (net (code "63") (name "Net-(Q18-S)") (class "Default")
      (node (ref "Q18") (pin "2") (pinfunction "S_2") (pintype "passive"))
      (node (ref "R34") (pin "2") (pinfunction "2_2") (pintype "passive"))
    )
    (net (code "64") (name "Net-(Q19-S)") (class "Default")
      (node (ref "Q19") (pin "2") (pinfunction "S_2") (pintype "passive"))
      (node (ref "R35") (pin "2") (pinfunction "2_2") (pintype "passive"))
    )
    (net (code "65") (name "Net-(R37-Pad2)") (class "Default")
      (node (ref "R37") (pin "2") (pinfunction "2_2") (pintype "passive"))
      (node (ref "SV1") (pin "4") (pinfunction "4_4") (pintype "passive"))
    )
    (net (code "66") (name "VDD") (class "Default")
      (node (ref "C33") (pin "1") (pinfunction "1_1") (pintype "passive"))
      (node (ref "C34") (pin "1") (pinfunction "1_1") (pintype "passive"))
      (node (ref "R11") (pin "2") (pinfunction "2_2") (pintype "passive"))
      (node (ref "R15") (pin "2") (pinfunction "2_2") (pintype "passive"))
      (node (ref "R19") (pin "2") (pinfunction "2_2") (pintype "passive"))
      (node (ref "R23") (pin "2") (pinfunction "2_2") (pintype "passive"))
      (node (ref "R27") (pin "2") (pinfunction "2_2") (pintype "passive"))
      (node (ref "R3") (pin "2") (pinfunction "2_2") (pintype "passive"))
      (node (ref "R31") (pin "2") (pinfunction "2_2") (pintype "passive"))
      (node (ref "R7") (pin "2") (pinfunction "2_2") (pintype "passive"))
      (node (ref "SENSOR") (pin "2") (pinfunction "KL_2") (pintype "passive"))
      (node (ref "X1") (pin "2") (pinfunction "1_2") (pintype "passive"))
      (node (ref "X2") (pin "2") (pinfunction "1_2") (pintype "passive"))
      (node (ref "X3") (pin "2") (pinfunction "1_2") (pintype "passive"))
      (node (ref "X4") (pin "2") (pinfunction "1_2") (pintype "passive"))
      (node (ref "X5") (pin "2") (pinfunction "1_2") (pintype "passive"))
      (node (ref "X6") (pin "2") (pinfunction "1_2") (pintype "passive"))
      (node (ref "X7") (pin "2") (pinfunction "1_2") (pintype "passive"))
      (node (ref "X8") (pin "2") (pinfunction "1_2") (pintype "passive"))
    )
    (net (code "67") (name "unconnected-(SV1-Pad5)") (class "Default")
      (node (ref "SV1") (pin "5") (pinfunction "5_5") (pintype "passive"))
    )
    (net (code "68") (name "unconnected-(SV1-Pad6)") (class "Default")
      (node (ref "SV1") (pin "6") (pinfunction "6_6") (pintype "passive"))
    )
  )
)
